# Power.net
KiCad netlist of a schematic drawn in Altium Designer
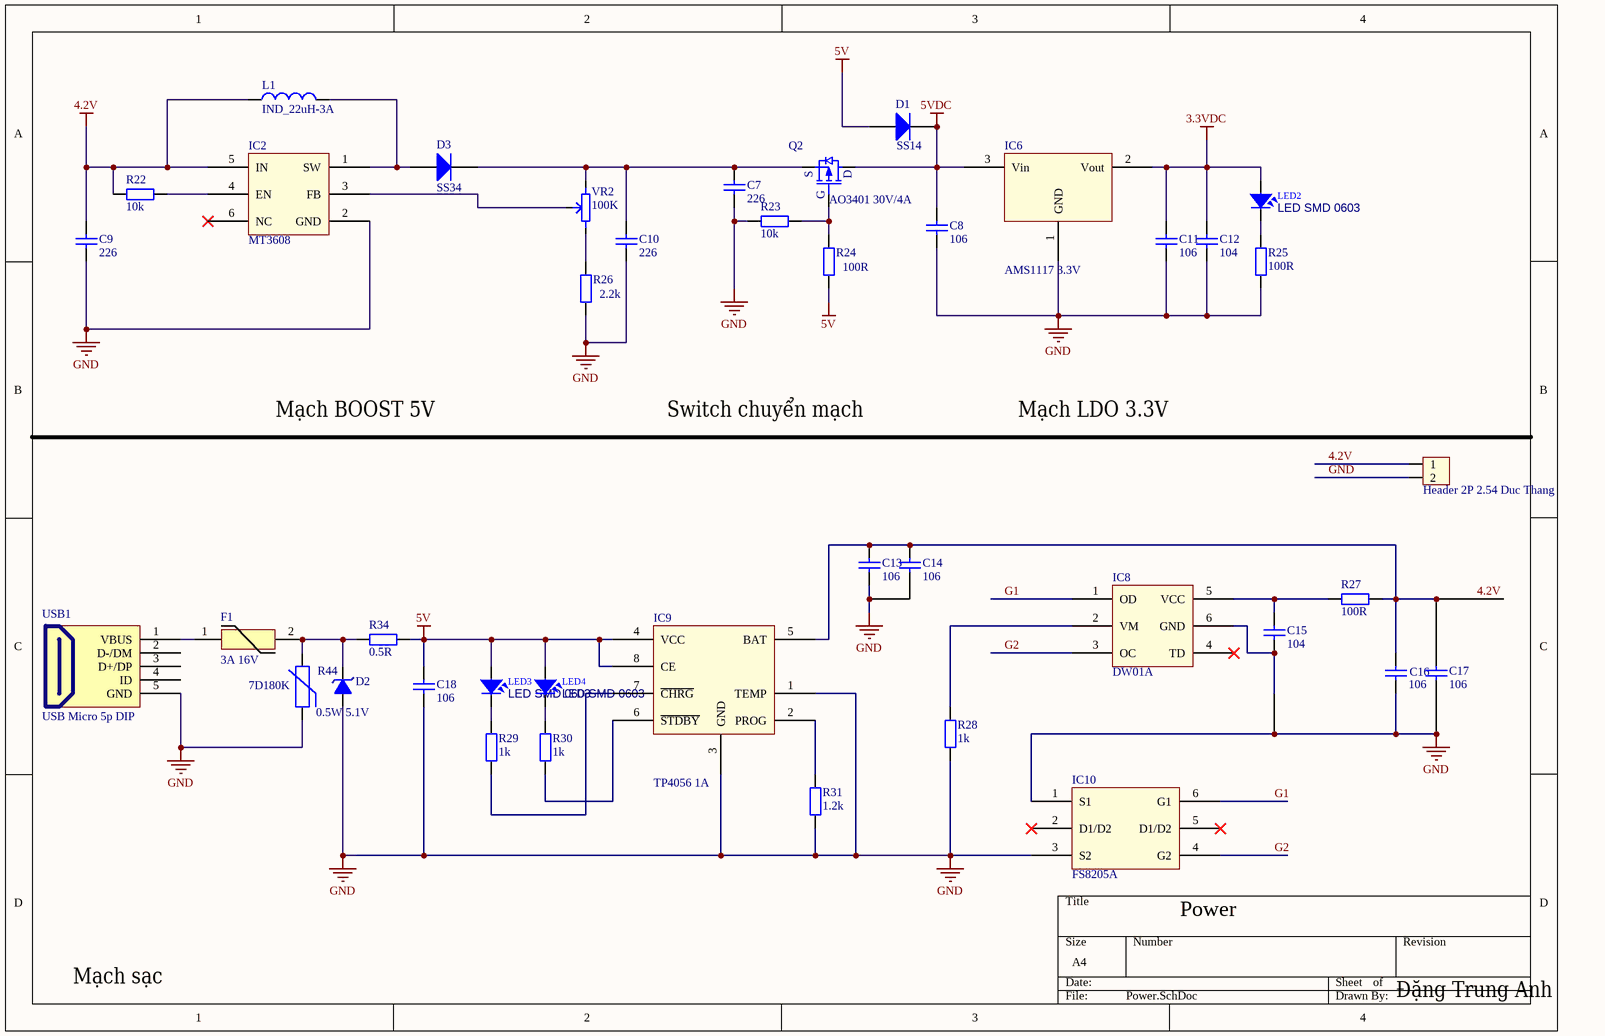
[diagram p0: Power.SchDoc]

(export (version "E")
  (design (tool "Eeschema 10.0.6"))
  (components
    (comp (ref "C7")
      (value "226")
      (footprint "tu 0603")
      (description "Dán")
      (libsource (lib "Altium_Lib_by_KhueNguyenCreator") (part "Tu 0603 226 6.3V 10%"))
    )
    (comp (ref "C8")
      (value "106")
      (footprint "tu 0603")
      (description "Dán")
      (libsource (lib "THU VIEN SCH") (part "Tu 0603 106 16V 20%"))
    )
    (comp (ref "C9")
      (value "226")
      (footprint "tu 0603")
      (description "Dán")
      (libsource (lib "Altium_Lib_by_KhueNguyenCreator") (part "Tu 0603 226 6.3V 10%"))
    )
    (comp (ref "C10")
      (value "226")
      (footprint "tu 0603")
      (description "Dán")
      (libsource (lib "Altium_Lib_by_KhueNguyenCreator") (part "Tu 0603 226 6.3V 10%"))
    )
    (comp (ref "C11")
      (value "106")
      (footprint "tu 0603")
      (description "Dán")
      (libsource (lib "THU VIEN SCH") (part "Tu 0603 106 16V 20%"))
    )
    (comp (ref "C12")
      (value "104")
      (footprint "tu 0603")
      (description "Dán")
      (libsource (lib "Altium_Lib_by_KhueNguyenCreator") (part "Tu 0603 104 50V 10%"))
    )
    (comp (ref "C13")
      (value "106")
      (footprint "tu 0603")
      (description "Dán")
      (libsource (lib "THU VIEN SCH") (part "Tu 0603 106 16V 20%"))
    )
    (comp (ref "C14")
      (value "106")
      (footprint "tu 0603")
      (description "Dán")
      (libsource (lib "THU VIEN SCH") (part "Tu 0603 106 16V 20%"))
    )
    (comp (ref "C15")
      (value "104")
      (footprint "tu 0603")
      (description "Dán")
      (libsource (lib "Altium_Lib_by_KhueNguyenCreator") (part "Tu 0603 104 50V 10%"))
    )
    (comp (ref "C16")
      (value "106")
      (footprint "tu 0603")
      (description "Dán")
      (libsource (lib "THU VIEN SCH") (part "Tu 0603 106 16V 20%"))
    )
    (comp (ref "C17")
      (value "106")
      (footprint "tu 0603")
      (description "Dán")
      (libsource (lib "THU VIEN SCH") (part "Tu 0603 106 16V 20%"))
    )
    (comp (ref "C18")
      (value "106")
      (footprint "tu 0603")
      (description "Dán")
      (libsource (lib "THU VIEN SCH") (part "Tu 0603 106 16V 20%"))
    )
    (comp (ref "D1")
      (value "SS14")
      (footprint "DIODE SMA")
      (description "Dán")
      (libsource (lib "Altium_Lib_by_KhueNguyenCreator") (part "Diode SS14 ( 1N5819)"))
    )
    (comp (ref "D2")
      (value "0.5W 5.1V")
      (footprint "DIODE ZENNER SMD SOD80")
      (description "Dán")
      (libsource (lib "Altium_Lib_by_KhueNguyenCreator") (part "Diode Zener 5.1V"))
    )
    (comp (ref "D3")
      (value "SS34")
      (footprint "DIODE SMA")
      (description "Dán")
      (libsource (lib "Altium_Lib_by_KhueNguyenCreator") (part "Diode SS34 ( 1N5822 )"))
    )
    (comp (ref "F1")
      (value "3A 16V")
      (footprint "FUSE-RUEF250U-2")
      (description "FUSE POLYSWITCH RUE SERIES 3A 16V")
      (fields (field (name "MPN") "RUEF250U-2"))
      (libsource (lib "BYTECH_HW_LIB_2019 (1)") (part "Cau chi tu phuc hoi 3A 16V"))
    )
    (comp (ref "H1")
      (value "Header 2P 2.54 Duc Thang")
      (footprint "XH2.54M-2")
      (description "Cắm")
      (libsource (lib "Altium_Lib_by_KhueNguyenCreator") (part "Header 2P 2.54 Duc Thang"))
    )
    (comp (ref "IC2")
      (value "MT3608")
      (footprint "SOT23-6A")
      (libsource (lib "Integrated_Library") (part "MT3608_Boost"))
    )
    (comp (ref "IC6")
      (value "AMS1117 3.3V")
      (footprint "SOT223")
      (libsource (lib "Integrated_Library") (part "AMS1117 3.3V"))
    )
    (comp (ref "IC8")
      (value "DW01A")
      (footprint "SOT23127P600-8N")
      (libsource (lib "Integrated_Library") (part "DW01A"))
    )
    (comp (ref "IC9")
      (value "TP4056 1A")
      (footprint "SOP8")
      (libsource (lib "Integrated_Library") (part "TP4056 1A"))
    )
    (comp (ref "IC10")
      (value "FS8205A")
      (footprint "SOT-23-6L")
      (libsource (lib "Integrated_Library") (part "FS8205A"))
    )
    (comp (ref "L1")
      (value "IND_22uH-3A")
      (footprint "IND_22_10X10_SMD")
      (description "Fixed Inductors MSS1038 SMT Shielded 15 uH 20 % 3.8 A")
      (fields
        (field (name "MANUFACTURER") "Bourns")
        (field (name "MANUFACTURER PART NUMBER") "MSS1038-153MLC")
      )
      (libsource (lib "Altium_Lib_by_KhueNguyenCreator") (part "IND_22uH-3A-30%-SMD_1"))
    )
    (comp (ref "LED2")
      (value "LED SMD 0603")
      (footprint "LED-0603-RED")
      (description "LED 0603 SMD Green 525nm 350mcd 20mA")
      (libsource (lib "My library altium") (part "LED SMD 0603"))
    )
    (comp (ref "LED3")
      (value "LED SMD 0603")
      (footprint "LED-0603-RED")
      (description "LED 0603 SMD Green 525nm 350mcd 20mA")
      (libsource (lib "My library altium") (part "LED SMD 0603"))
    )
    (comp (ref "LED4")
      (value "LED SMD 0603")
      (footprint "LED-0603-BLUE")
      (description "LED 0603 SMD Green 525nm 350mcd 20mA")
      (libsource (lib "My library altium") (part "LED SMD 0603"))
    )
    (comp (ref "Q2")
      (value "AO3401 30V/4A")
      (footprint "SOT23_3")
      (description "MOSFET P-CH 30V 4A SOT23")
      (fields (field (name "MPN") "AO3415") (field (name "MFR") "Alpha & Omega Semiconductor Inc."))
      (libsource (lib "BYTECH_HW_LIB_2019 (1)") (part "AO3401"))
    )
    (comp (ref "R22")
      (value "10k")
      (footprint "tro smd 0603")
      (description "Dán")
      (libsource (lib "Altium_Lib_by_KhueNguyenCreator") (part "Tro 0603 5% 10k"))
    )
    (comp (ref "R23")
      (value "10k")
      (footprint "tro smd 0603")
      (description "Dán")
      (libsource (lib "Altium_Lib_by_KhueNguyenCreator") (part "Tro 0603 5% 10k"))
    )
    (comp (ref "R24")
      (value "100R")
      (footprint "tro smd 0603")
      (description "Dán")
      (libsource (lib "Altium_Lib_by_KhueNguyenCreator") (part "Tro 0603 5% 100R"))
    )
    (comp (ref "R25")
      (value "100R")
      (footprint "tro smd 0603")
      (description "Dán")
      (libsource (lib "Altium_Lib_by_KhueNguyenCreator") (part "Tro 0603 5% 100R"))
    )
    (comp (ref "R26")
      (value "2.2k")
      (footprint "tro smd 0603")
      (description "Dán")
      (libsource (lib "Altium_Lib_by_KhueNguyenCreator") (part "Tro 0603 5% 2.2k"))
    )
    (comp (ref "R27")
      (value "100R")
      (footprint "tro smd 0603")
      (description "Dán")
      (libsource (lib "Altium_Lib_by_KhueNguyenCreator") (part "Tro 0603 5% 100R"))
    )
    (comp (ref "R28")
      (value "1k")
      (footprint "tro smd 0603")
      (description "Dán")
      (libsource (lib "Altium_Lib_by_KhueNguyenCreator") (part "Tro 0603 5% 1k"))
    )
    (comp (ref "R29")
      (value "1k")
      (footprint "tro smd 0603")
      (description "Dán")
      (libsource (lib "Altium_Lib_by_KhueNguyenCreator") (part "Tro 0603 5% 1k"))
    )
    (comp (ref "R30")
      (value "1k")
      (footprint "tro smd 0603")
      (description "Dán")
      (libsource (lib "Altium_Lib_by_KhueNguyenCreator") (part "Tro 0603 5% 1k"))
    )
    (comp (ref "R31")
      (value "1.2k")
      (footprint "tro smd 0603")
      (description "Dán")
      (libsource (lib "Altium_Lib_by_KhueNguyenCreator") (part "Tro 0603 1% 1.2k"))
    )
    (comp (ref "R34")
      (value "0.5R")
      (footprint "tro smd 0805")
      (description "Dán")
      (libsource (lib "THU VIEN SCH") (part "Tro 0805 5% 0.5R"))
    )
    (comp (ref "R44")
      (value "7D180K")
      (footprint "VARISTOR-7D180K")
      (description "VARISTOR 7V 18A DISC 7MM")
      (fields (field (name "MPN") "V47ZA1P"))
      (libsource (lib "BYTECH_HW_LIB_2019 (1)") (part "Varistor 7D180K"))
    )
    (comp (ref "USB1")
      (value "USB Micro 5p DIP")
      (footprint "USB Micro 5p DIP")
      (description "USB Type B")
      (libsource (lib "Altium_Lib_by_KhueNguyenCreator") (part "USB Micro 5p DIP"))
    )
    (comp (ref "VR2")
      (value "100K")
      (footprint "Bien Tro Tam Giac Dung")
      (description "Cắm")
      (libsource (lib "Altium_Lib_by_KhueNguyenCreator") (part "Bien tro tam giac 100K Dung"))
    )
  )
  (nets
    (net (code "1") (name "/G1") (class "Default")
      (node (ref "IC10") (pin "6") (pinfunction "G1_6") (pintype "passive"))
      (node (ref "IC8") (pin "1") (pinfunction "OD_1") (pintype "passive"))
    )
    (net (code "2") (name "/G2") (class "Default")
      (node (ref "IC10") (pin "4") (pinfunction "G2_4") (pintype "passive"))
      (node (ref "IC8") (pin "3") (pinfunction "OC_3") (pintype "passive"))
    )
    (net (code "3") (name "3.3VDC") (class "Default")
      (node (ref "C11") (pin "1") (pinfunction "1_1") (pintype "passive"))
      (node (ref "C12") (pin "1") (pinfunction "1_1") (pintype "passive"))
      (node (ref "IC6") (pin "2") (pinfunction "Vout_2") (pintype "passive"))
      (node (ref "LED2") (pin "A") (pinfunction "A_A") (pintype "passive"))
    )
    (net (code "4") (name "4.2V") (class "Default")
      (node (ref "C13") (pin "1") (pinfunction "1_1") (pintype "passive"))
      (node (ref "C14") (pin "1") (pinfunction "1_1") (pintype "passive"))
      (node (ref "C16") (pin "1") (pinfunction "1_1") (pintype "passive"))
      (node (ref "C17") (pin "1") (pinfunction "1_1") (pintype "passive"))
      (node (ref "C9") (pin "1") (pinfunction "1_1") (pintype "passive"))
      (node (ref "H1") (pin "1") (pinfunction "1_1") (pintype "passive"))
      (node (ref "IC2") (pin "5") (pinfunction "IN_5") (pintype "passive"))
      (node (ref "IC9") (pin "5") (pinfunction "BAT_5") (pintype "passive"))
      (node (ref "L1") (pin "1") (pinfunction "1_1") (pintype "passive"))
      (node (ref "R22") (pin "1") (pinfunction "1_1") (pintype "passive"))
      (node (ref "R27") (pin "1") (pinfunction "1_1") (pintype "passive"))
    )
    (net (code "5") (name "5V") (class "Default")
      (node (ref "C18") (pin "1") (pinfunction "1_1") (pintype "passive"))
      (node (ref "D1") (pin "1") (pinfunction "A_1") (pintype "passive"))
      (node (ref "IC9") (pin "4") (pinfunction "VCC_4") (pintype "passive"))
      (node (ref "IC9") (pin "8") (pinfunction "CE_8") (pintype "passive"))
      (node (ref "LED3") (pin "A") (pinfunction "A_A") (pintype "passive"))
      (node (ref "LED4") (pin "A") (pinfunction "A_A") (pintype "passive"))
      (node (ref "R24") (pin "1") (pinfunction "1_1") (pintype "passive"))
      (node (ref "R34") (pin "2") (pinfunction "2_2") (pintype "passive"))
    )
    (net (code "6") (name "5VDC") (class "Default")
      (node (ref "C8") (pin "1") (pinfunction "1_1") (pintype "passive"))
      (node (ref "D1") (pin "2") (pinfunction "K_2") (pintype "passive"))
      (node (ref "IC6") (pin "3") (pinfunction "Vin_3") (pintype "passive"))
      (node (ref "Q2") (pin "3") (pinfunction "D_3") (pintype "passive"))
    )
    (net (code "7") (name "GND") (class "Default")
      (node (ref "C10") (pin "2") (pinfunction "2_2") (pintype "passive"))
      (node (ref "C11") (pin "2") (pinfunction "2_2") (pintype "passive"))
      (node (ref "C12") (pin "2") (pinfunction "2_2") (pintype "passive"))
      (node (ref "C13") (pin "2") (pinfunction "2_2") (pintype "passive"))
      (node (ref "C14") (pin "2") (pinfunction "2_2") (pintype "passive"))
      (node (ref "C15") (pin "2") (pinfunction "2_2") (pintype "passive"))
      (node (ref "C16") (pin "2") (pinfunction "2_2") (pintype "passive"))
      (node (ref "C17") (pin "2") (pinfunction "2_2") (pintype "passive"))
      (node (ref "C18") (pin "2") (pinfunction "2_2") (pintype "passive"))
      (node (ref "C7") (pin "2") (pinfunction "2_2") (pintype "passive"))
      (node (ref "C8") (pin "2") (pinfunction "2_2") (pintype "passive"))
      (node (ref "C9") (pin "2") (pinfunction "2_2") (pintype "passive"))
      (node (ref "D2") (pin "1") (pinfunction "A_1") (pintype "passive"))
      (node (ref "H1") (pin "2") (pinfunction "2_2") (pintype "passive"))
      (node (ref "IC10") (pin "1") (pinfunction "S1_1") (pintype "passive"))
      (node (ref "IC10") (pin "3") (pinfunction "S2_3") (pintype "passive"))
      (node (ref "IC2") (pin "2") (pinfunction "GND_2") (pintype "passive"))
      (node (ref "IC6") (pin "1") (pinfunction "GND_1") (pintype "passive"))
      (node (ref "IC8") (pin "6") (pinfunction "GND_6") (pintype "passive"))
      (node (ref "IC9") (pin "1") (pinfunction "TEMP_1") (pintype "passive"))
      (node (ref "IC9") (pin "3") (pinfunction "GND_3") (pintype "passive"))
      (node (ref "R23") (pin "1") (pinfunction "1_1") (pintype "passive"))
      (node (ref "R25") (pin "1") (pinfunction "1_1") (pintype "passive"))
      (node (ref "R26") (pin "1") (pinfunction "1_1") (pintype "passive"))
      (node (ref "R28") (pin "1") (pinfunction "1_1") (pintype "passive"))
      (node (ref "R31") (pin "1") (pinfunction "1_1") (pintype "passive"))
      (node (ref "R44") (pin "1") (pinfunction "1_1") (pintype "passive"))
      (node (ref "USB1") (pin "5") (pinfunction "GND_5") (pintype "passive"))
    )
    (net (code "8") (name "Net-(D2-K)") (class "Default")
      (node (ref "D2") (pin "2") (pinfunction "K_2") (pintype "passive"))
      (node (ref "F1") (pin "2") (pinfunction "2_2") (pintype "passive"))
      (node (ref "R34") (pin "1") (pinfunction "1_1") (pintype "passive"))
      (node (ref "R44") (pin "2") (pinfunction "2_2") (pintype "passive"))
    )
    (net (code "9") (name "Net-(D3-A)") (class "Default")
      (node (ref "D3") (pin "1") (pinfunction "A_1") (pintype "passive"))
      (node (ref "IC2") (pin "1") (pinfunction "SW_1") (pintype "passive"))
      (node (ref "L1") (pin "2") (pinfunction "2_2") (pintype "passive"))
    )
    (net (code "10") (name "Net-(D3-K)") (class "Default")
      (node (ref "C10") (pin "1") (pinfunction "1_1") (pintype "passive"))
      (node (ref "C7") (pin "1") (pinfunction "1_1") (pintype "passive"))
      (node (ref "D3") (pin "2") (pinfunction "K_2") (pintype "passive"))
      (node (ref "Q2") (pin "2") (pinfunction "S_2") (pintype "passive"))
      (node (ref "VR2") (pin "3") (pinfunction "3_3") (pintype "passive"))
    )
    (net (code "11") (name "Net-(IC2-EN)") (class "Default")
      (node (ref "IC2") (pin "4") (pinfunction "EN_4") (pintype "passive"))
      (node (ref "R22") (pin "2") (pinfunction "2_2") (pintype "passive"))
    )
    (net (code "12") (name "Net-(IC2-FB)") (class "Default")
      (node (ref "IC2") (pin "3") (pinfunction "FB_3") (pintype "passive"))
      (node (ref "VR2") (pin "2") (pinfunction "2_2") (pintype "passive"))
    )
    (net (code "13") (name "Net-(IC8-VCC)") (class "Default")
      (node (ref "C15") (pin "1") (pinfunction "1_1") (pintype "passive"))
      (node (ref "IC8") (pin "5") (pinfunction "VCC_5") (pintype "passive"))
      (node (ref "R27") (pin "2") (pinfunction "2_2") (pintype "passive"))
    )
    (net (code "14") (name "Net-(IC8-VM)") (class "Default")
      (node (ref "IC8") (pin "2") (pinfunction "VM_2") (pintype "passive"))
      (node (ref "R28") (pin "2") (pinfunction "2_2") (pintype "passive"))
    )
    (net (code "15") (name "Net-(IC9-PROG)") (class "Default")
      (node (ref "IC9") (pin "2") (pinfunction "PROG_2") (pintype "passive"))
      (node (ref "R31") (pin "2") (pinfunction "2_2") (pintype "passive"))
    )
    (net (code "16") (name "Net-(IC9-~{CHRG})") (class "Default")
      (node (ref "IC9") (pin "7") (pinfunction "~{CHRG}_7") (pintype "passive"))
      (node (ref "R29") (pin "1") (pinfunction "1_1") (pintype "passive"))
    )
    (net (code "17") (name "Net-(IC9-~{STDBY})") (class "Default")
      (node (ref "IC9") (pin "6") (pinfunction "~{STDBY}_6") (pintype "passive"))
      (node (ref "R30") (pin "1") (pinfunction "1_1") (pintype "passive"))
    )
    (net (code "18") (name "Net-(LED2-PadK)") (class "Default")
      (node (ref "LED2") (pin "K") (pinfunction "K_K") (pintype "passive"))
      (node (ref "R25") (pin "2") (pinfunction "2_2") (pintype "passive"))
    )
    (net (code "19") (name "Net-(LED3-PadK)") (class "Default")
      (node (ref "LED3") (pin "K") (pinfunction "K_K") (pintype "passive"))
      (node (ref "R29") (pin "2") (pinfunction "2_2") (pintype "passive"))
    )
    (net (code "20") (name "Net-(LED4-PadK)") (class "Default")
      (node (ref "LED4") (pin "K") (pinfunction "K_K") (pintype "passive"))
      (node (ref "R30") (pin "2") (pinfunction "2_2") (pintype "passive"))
    )
    (net (code "21") (name "Net-(Q2-G)") (class "Default")
      (node (ref "Q2") (pin "1") (pinfunction "G_1") (pintype "passive"))
      (node (ref "R23") (pin "2") (pinfunction "2_2") (pintype "passive"))
      (node (ref "R24") (pin "2") (pinfunction "2_2") (pintype "passive"))
    )
    (net (code "22") (name "Net-(R26-Pad2)") (class "Default")
      (node (ref "R26") (pin "2") (pinfunction "2_2") (pintype "passive"))
      (node (ref "VR2") (pin "1") (pinfunction "1_1") (pintype "passive"))
    )
    (net (code "23") (name "Net-(USB1-VBUS)") (class "Default")
      (node (ref "F1") (pin "1") (pinfunction "1_1") (pintype "passive"))
      (node (ref "USB1") (pin "1") (pinfunction "VBUS_1") (pintype "passive"))
    )
    (net (code "24") (name "unconnected-(IC2-NC-Pad6)") (class "Default")
      (node (ref "IC2") (pin "6") (pinfunction "NC_6") (pintype "passive+no_connect"))
    )
    (net (code "25") (name "unconnected-(IC8-TD-Pad4)") (class "Default")
      (node (ref "IC8") (pin "4") (pinfunction "TD_4") (pintype "passive+no_connect"))
    )
    (net (code "26") (name "unconnected-(IC10-D1{slash}D2-Pad2)") (class "Default")
      (node (ref "IC10") (pin "2") (pinfunction "D1/D2_2") (pintype "passive+no_connect"))
    )
    (net (code "27") (name "unconnected-(IC10-D1{slash}D2-Pad5)") (class "Default")
      (node (ref "IC10") (pin "5") (pinfunction "D1/D2_5") (pintype "passive+no_connect"))
    )
    (net (code "28") (name "unconnected-(USB1-D+{slash}DP-Pad3)") (class "Default")
      (node (ref "USB1") (pin "3") (pinfunction "D+/DP_3") (pintype "passive"))
    )
    (net (code "29") (name "unconnected-(USB1-D-{slash}DM-Pad2)") (class "Default")
      (node (ref "USB1") (pin "2") (pinfunction "D-/DM_2") (pintype "passive"))
    )
    (net (code "30") (name "unconnected-(USB1-ID-Pad4)") (class "Default")
      (node (ref "USB1") (pin "4") (pinfunction "ID_4") (pintype "passive"))
    )
  )
)
